# 7segement4digits1badidea-feathershield-m.net
KiCad netlist of a schematic drawn in EAGLE
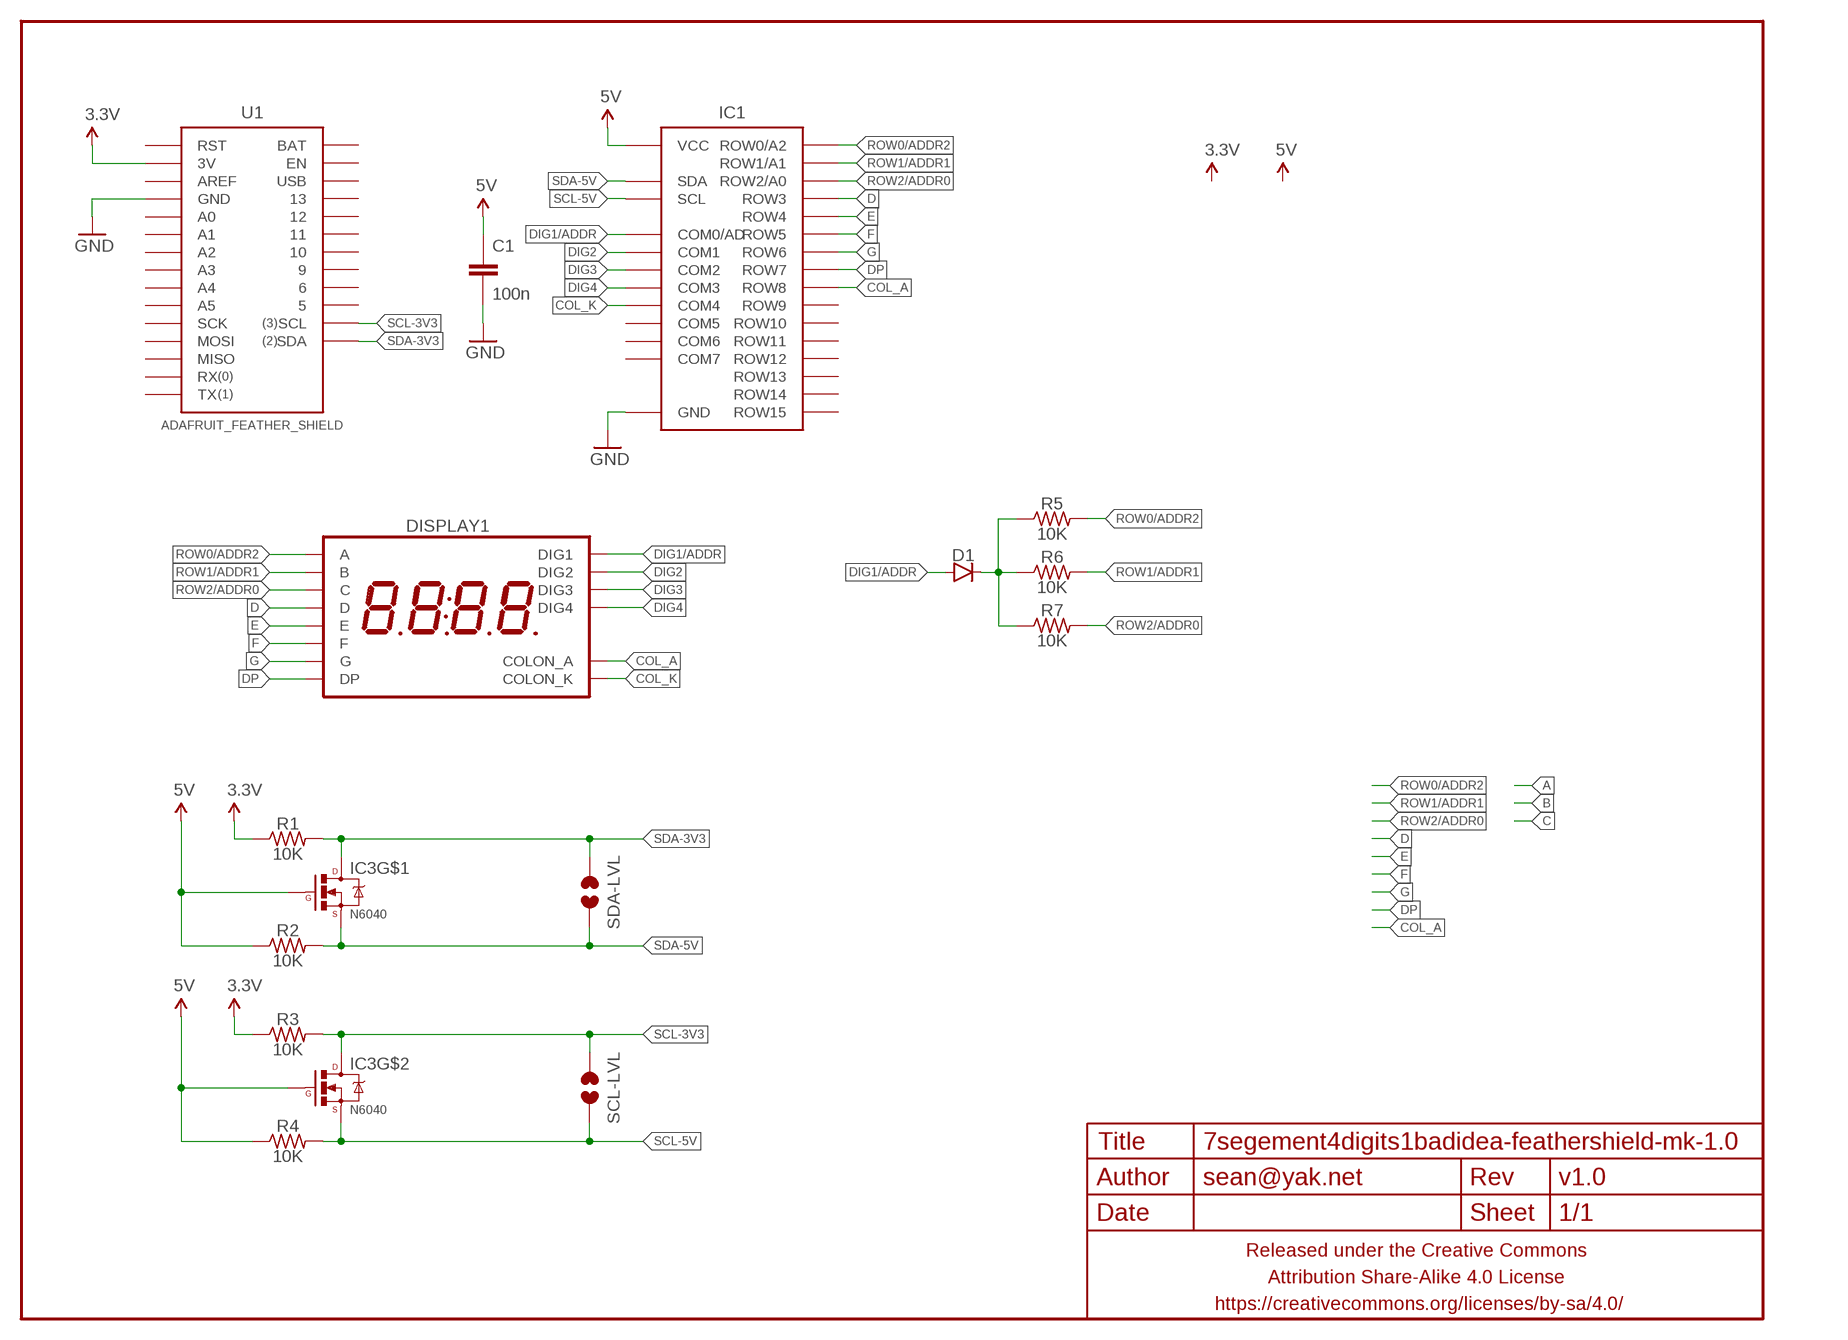
[diagram p0: schematic, sheet 1]

(export (version "E")
  (design (tool "Eeschema 10.0.6"))
  (components
    (comp (ref "C1")
      (value "100n")
      (footprint "eagle-import:C0603")
      (libsource (lib "eagle-import") (part "CAPACITOR-CERAMICC0603"))
    )
    (comp (ref "D1")
      (value "DIODESOT23")
      (footprint "eagle-import:SOT23")
      (libsource (lib "eagle-import") (part "DIODESOT23"))
    )
    (comp (ref "DISPLAY1")
      (value "7SEG_4DIGIT_COLON14.2MM-CC")
      (footprint "eagle-import:7SEG_4DIG_0.56IN_14MM_ADAFRUIT")
      (libsource (lib "eagle-import") (part "7SEG_4DIGIT_COLON14.2MM-CC"))
    )
    (comp (ref "FRAME1")
      (value "FRAME-LETTERNO_PACKAGE")
      (footprint "eagle-import:DUMMY")
      (fields (field (name "DESIGNER") "sean@yak.net") (field (name "VERSION") "v1.0"))
      (libsource (lib "eagle-import") (part "FRAME-LETTERNO_PACKAGE"))
    )
    (comp (ref "IC1")
      (value "HT16K33")
      (footprint "eagle-import:SOIC28W")
      (libsource (lib "eagle-import") (part "HT16K33-28SOIC28W"))
    )
    (comp (ref "IC3")
      (value "N6040")
      (footprint "eagle-import:SO08")
      (libsource (lib "eagle-import") (part "MOSFET-NCHANNEL-DUALSOIC8"))
    )
    (comp (ref "R1")
      (value "10K")
      (footprint "eagle-import:R0603")
      (libsource (lib "eagle-import") (part "RESISTORR0603"))
    )
    (comp (ref "R2")
      (value "10K")
      (footprint "eagle-import:R0603")
      (libsource (lib "eagle-import") (part "RESISTORR0603"))
    )
    (comp (ref "R3")
      (value "10K")
      (footprint "eagle-import:R0603")
      (libsource (lib "eagle-import") (part "RESISTORR0603"))
    )
    (comp (ref "R4")
      (value "10K")
      (footprint "eagle-import:R0603")
      (libsource (lib "eagle-import") (part "RESISTORR0603"))
    )
    (comp (ref "R5")
      (value "10K")
      (footprint "eagle-import:R0603")
      (libsource (lib "eagle-import") (part "RESISTORR0603"))
    )
    (comp (ref "R6")
      (value "10K")
      (footprint "eagle-import:R0603")
      (libsource (lib "eagle-import") (part "RESISTORR0603"))
    )
    (comp (ref "R7")
      (value "10K")
      (footprint "eagle-import:R0603")
      (libsource (lib "eagle-import") (part "RESISTORR0603"))
    )
    (comp (ref "SCL-LVL")
      (value "JUMPER-PAD-2-NOYES_SILK")
      (footprint "eagle-import:PAD-JUMPER-2-NO_YES_SILK")
      (libsource (lib "eagle-import") (part "JUMPER-PAD-2-NOYES_SILK"))
    )
    (comp (ref "SDA-LVL")
      (value "JUMPER-PAD-2-NOYES_SILK")
      (footprint "eagle-import:PAD-JUMPER-2-NO_YES_SILK")
      (libsource (lib "eagle-import") (part "JUMPER-PAD-2-NOYES_SILK"))
    )
    (comp (ref "U1")
      (value "ADAFRUIT_FEATHER_SHIELD")
      (footprint "eagle-import:ADAFRUIT_FEATHER")
      (libsource (lib "eagle-import") (part "ADAFRUIT_FEATHER_SHIELD"))
    )
  )
  (nets
    (net (code "1") (name "3.3V") (class "Default")
      (node (ref "R1") (pin "1") (pinfunction "1_1") (pintype "passive"))
      (node (ref "R3") (pin "1") (pinfunction "1_1") (pintype "passive"))
      (node (ref "U1") (pin "3V") (pinfunction "3V_3V") (pintype "bidirectional"))
    )
    (net (code "2") (name "5V") (class "Default")
      (node (ref "C1") (pin "1") (pinfunction "1_1") (pintype "passive"))
      (node (ref "IC1") (pin "28") (pinfunction "VCC_28") (pintype "bidirectional"))
      (node (ref "IC3") (pin "2") (pinfunction "G_2") (pintype "passive"))
      (node (ref "IC3") (pin "4") (pinfunction "G_4") (pintype "passive"))
      (node (ref "R2") (pin "1") (pinfunction "1_1") (pintype "passive"))
      (node (ref "R4") (pin "1") (pinfunction "1_1") (pintype "passive"))
    )
    (net (code "6") (name "COL_A") (class "Default")
      (node (ref "DISPLAY1") (pin "P$8") (pinfunction "COLON_A_P$8") (pintype "passive"))
      (node (ref "IC1") (pin "17") (pinfunction "ROW8_17") (pintype "bidirectional"))
    )
    (net (code "7") (name "COL_K") (class "Default")
      (node (ref "DISPLAY1") (pin "P$7") (pinfunction "COLON_K_P$7") (pintype "passive"))
      (node (ref "IC1") (pin "6") (pinfunction "COM4_6") (pintype "bidirectional"))
    )
    (net (code "8") (name "D") (class "Default")
      (node (ref "DISPLAY1") (pin "P$2") (pinfunction "D_P$2") (pintype "passive"))
      (node (ref "IC1") (pin "22") (pinfunction "ROW3_22") (pintype "bidirectional"))
    )
    (net (code "9") (name "DIG1{slash}ADDR") (class "Default")
      (node (ref "D1") (pin "1") (pinfunction "A_1") (pintype "passive"))
      (node (ref "DISPLAY1") (pin "P$14") (pinfunction "DIG1_P$14") (pintype "passive"))
      (node (ref "IC1") (pin "2") (pinfunction "COM0/AD_2") (pintype "bidirectional"))
    )
    (net (code "10") (name "DIG2") (class "Default")
      (node (ref "DISPLAY1") (pin "P$11") (pinfunction "DIG2_P$11") (pintype "passive"))
      (node (ref "IC1") (pin "3") (pinfunction "COM1_3") (pintype "bidirectional"))
    )
    (net (code "11") (name "DIG3") (class "Default")
      (node (ref "DISPLAY1") (pin "P$10") (pinfunction "DIG3_P$10") (pintype "passive"))
      (node (ref "IC1") (pin "4") (pinfunction "COM2_4") (pintype "bidirectional"))
    )
    (net (code "12") (name "DIG4") (class "Default")
      (node (ref "DISPLAY1") (pin "P$6") (pinfunction "DIG4_P$6") (pintype "passive"))
      (node (ref "IC1") (pin "5") (pinfunction "COM3_5") (pintype "bidirectional"))
    )
    (net (code "13") (name "DP") (class "Default")
      (node (ref "DISPLAY1") (pin "P$3") (pinfunction "DP_P$3") (pintype "passive"))
      (node (ref "IC1") (pin "18") (pinfunction "ROW7_18") (pintype "bidirectional"))
    )
    (net (code "14") (name "E") (class "Default")
      (node (ref "DISPLAY1") (pin "P$1") (pinfunction "E_P$1") (pintype "passive"))
      (node (ref "IC1") (pin "21") (pinfunction "ROW4_21") (pintype "bidirectional"))
    )
    (net (code "15") (name "F") (class "Default")
      (node (ref "DISPLAY1") (pin "P$12") (pinfunction "F_P$12") (pintype "passive"))
      (node (ref "IC1") (pin "20") (pinfunction "ROW5_20") (pintype "bidirectional"))
    )
    (net (code "16") (name "G") (class "Default")
      (node (ref "DISPLAY1") (pin "P$5") (pinfunction "G_P$5") (pintype "passive"))
      (node (ref "IC1") (pin "19") (pinfunction "ROW6_19") (pintype "bidirectional"))
    )
    (net (code "17") (name "GND") (class "Default")
      (node (ref "C1") (pin "2") (pinfunction "2_2") (pintype "passive"))
      (node (ref "IC1") (pin "1") (pinfunction "GND_1") (pintype "bidirectional"))
      (node (ref "U1") (pin "GND@0") (pinfunction "GND_GND@0") (pintype "bidirectional"))
      (node (ref "U1") (pin "GND@1") (pinfunction "GND_GND@1") (pintype "bidirectional"))
    )
    (net (code "18") (name "Net-(D1-C)") (class "Default")
      (node (ref "D1") (pin "3") (pinfunction "C_3") (pintype "passive"))
      (node (ref "R5") (pin "1") (pinfunction "1_1") (pintype "passive"))
      (node (ref "R6") (pin "1") (pinfunction "1_1") (pintype "passive"))
      (node (ref "R7") (pin "1") (pinfunction "1_1") (pintype "passive"))
    )
    (net (code "19") (name "ROW0{slash}ADDR2") (class "Default")
      (node (ref "DISPLAY1") (pin "P$13") (pinfunction "A_P$13") (pintype "passive"))
      (node (ref "IC1") (pin "25") (pinfunction "ROW0/A2_25") (pintype "bidirectional"))
      (node (ref "R5") (pin "2") (pinfunction "2_2") (pintype "passive"))
    )
    (net (code "20") (name "ROW1{slash}ADDR1") (class "Default")
      (node (ref "DISPLAY1") (pin "P$9") (pinfunction "B_P$9") (pintype "passive"))
      (node (ref "IC1") (pin "24") (pinfunction "ROW1/A1_24") (pintype "bidirectional"))
      (node (ref "R6") (pin "2") (pinfunction "2_2") (pintype "passive"))
    )
    (net (code "21") (name "ROW2{slash}ADDR0") (class "Default")
      (node (ref "DISPLAY1") (pin "P$4") (pinfunction "C_P$4") (pintype "passive"))
      (node (ref "IC1") (pin "23") (pinfunction "ROW2/A0_23") (pintype "bidirectional"))
      (node (ref "R7") (pin "2") (pinfunction "2_2") (pintype "passive"))
    )
    (net (code "22") (name "SCL-3V3") (class "Default")
      (node (ref "IC3") (pin "5") (pinfunction "D_5") (pintype "passive"))
      (node (ref "IC3") (pin "6") (pinfunction "D_6") (pintype "passive"))
      (node (ref "R3") (pin "2") (pinfunction "2_2") (pintype "passive"))
      (node (ref "SCL-LVL") (pin "1") (pinfunction "1_1") (pintype "passive"))
      (node (ref "U1") (pin "SCL") (pinfunction "SCL_SCL") (pintype "bidirectional"))
    )
    (net (code "23") (name "SCL-5V") (class "Default")
      (node (ref "IC1") (pin "26") (pinfunction "SCL_26") (pintype "bidirectional"))
      (node (ref "IC3") (pin "3") (pinfunction "S_3") (pintype "passive"))
      (node (ref "R4") (pin "2") (pinfunction "2_2") (pintype "passive"))
      (node (ref "SCL-LVL") (pin "2") (pinfunction "2_2") (pintype "passive"))
    )
    (net (code "24") (name "SDA-3V3") (class "Default")
      (node (ref "IC3") (pin "7") (pinfunction "D_7") (pintype "passive"))
      (node (ref "IC3") (pin "8") (pinfunction "D_8") (pintype "passive"))
      (node (ref "R1") (pin "2") (pinfunction "2_2") (pintype "passive"))
      (node (ref "SDA-LVL") (pin "1") (pinfunction "1_1") (pintype "passive"))
      (node (ref "U1") (pin "SDA") (pinfunction "SDA_SDA") (pintype "bidirectional"))
    )
    (net (code "25") (name "SDA-5V") (class "Default")
      (node (ref "IC1") (pin "27") (pinfunction "SDA_27") (pintype "bidirectional"))
      (node (ref "IC3") (pin "1") (pinfunction "S_1") (pintype "passive"))
      (node (ref "R2") (pin "2") (pinfunction "2_2") (pintype "passive"))
      (node (ref "SDA-LVL") (pin "2") (pinfunction "2_2") (pintype "passive"))
    )
    (net (code "26") (name "unconnected-(IC1-COM5-Pad7)") (class "Default")
      (node (ref "IC1") (pin "7") (pinfunction "COM5_7") (pintype "bidirectional"))
    )
    (net (code "27") (name "unconnected-(IC1-COM6-Pad8)") (class "Default")
      (node (ref "IC1") (pin "8") (pinfunction "COM6_8") (pintype "bidirectional"))
    )
    (net (code "28") (name "unconnected-(IC1-COM7-Pad9)") (class "Default")
      (node (ref "IC1") (pin "9") (pinfunction "COM7_9") (pintype "bidirectional"))
    )
    (net (code "29") (name "unconnected-(IC1-ROW9-Pad16)") (class "Default")
      (node (ref "IC1") (pin "16") (pinfunction "ROW9_16") (pintype "bidirectional"))
    )
    (net (code "30") (name "unconnected-(IC1-ROW10-Pad15)") (class "Default")
      (node (ref "IC1") (pin "15") (pinfunction "ROW10_15") (pintype "bidirectional"))
    )
    (net (code "31") (name "unconnected-(IC1-ROW11-Pad14)") (class "Default")
      (node (ref "IC1") (pin "14") (pinfunction "ROW11_14") (pintype "bidirectional"))
    )
    (net (code "32") (name "unconnected-(IC1-ROW12-Pad13)") (class "Default")
      (node (ref "IC1") (pin "13") (pinfunction "ROW12_13") (pintype "bidirectional"))
    )
    (net (code "33") (name "unconnected-(IC1-ROW13-Pad12)") (class "Default")
      (node (ref "IC1") (pin "12") (pinfunction "ROW13_12") (pintype "bidirectional"))
    )
    (net (code "34") (name "unconnected-(IC1-ROW14-Pad11)") (class "Default")
      (node (ref "IC1") (pin "11") (pinfunction "ROW14_11") (pintype "bidirectional"))
    )
    (net (code "35") (name "unconnected-(IC1-ROW15-Pad10)") (class "Default")
      (node (ref "IC1") (pin "10") (pinfunction "ROW15_10") (pintype "bidirectional"))
    )
    (net (code "36") (name "unconnected-(U1-Pad5)") (class "Default")
      (node (ref "U1") (pin "5") (pinfunction "5_5") (pintype "bidirectional"))
    )
    (net (code "37") (name "unconnected-(U1-Pad6)") (class "Default")
      (node (ref "U1") (pin "6") (pinfunction "6_6") (pintype "bidirectional"))
    )
    (net (code "38") (name "unconnected-(U1-Pad9)") (class "Default")
      (node (ref "U1") (pin "9") (pinfunction "9_9") (pintype "bidirectional"))
    )
    (net (code "39") (name "unconnected-(U1-Pad10)") (class "Default")
      (node (ref "U1") (pin "10") (pinfunction "10_10") (pintype "bidirectional"))
    )
    (net (code "40") (name "unconnected-(U1-Pad11)") (class "Default")
      (node (ref "U1") (pin "11") (pinfunction "11_11") (pintype "bidirectional"))
    )
    (net (code "41") (name "unconnected-(U1-Pad12)") (class "Default")
      (node (ref "U1") (pin "12") (pinfunction "12_12") (pintype "bidirectional"))
    )
    (net (code "42") (name "unconnected-(U1-Pad13)") (class "Default")
      (node (ref "U1") (pin "13") (pinfunction "13_13") (pintype "bidirectional"))
    )
    (net (code "43") (name "unconnected-(U1-PadA0)") (class "Default")
      (node (ref "U1") (pin "A0") (pinfunction "A0_A0") (pintype "bidirectional"))
    )
    (net (code "44") (name "unconnected-(U1-PadA1)") (class "Default")
      (node (ref "U1") (pin "A1") (pinfunction "A1_A1") (pintype "bidirectional"))
    )
    (net (code "45") (name "unconnected-(U1-PadA2)") (class "Default")
      (node (ref "U1") (pin "A2") (pinfunction "A2_A2") (pintype "bidirectional"))
    )
    (net (code "46") (name "unconnected-(U1-PadA3)") (class "Default")
      (node (ref "U1") (pin "A3") (pinfunction "A3_A3") (pintype "bidirectional"))
    )
    (net (code "47") (name "unconnected-(U1-PadA4)") (class "Default")
      (node (ref "U1") (pin "A4") (pinfunction "A4_A4") (pintype "bidirectional"))
    )
    (net (code "48") (name "unconnected-(U1-PadA5)") (class "Default")
      (node (ref "U1") (pin "A5") (pinfunction "A5_A5") (pintype "bidirectional"))
    )
    (net (code "49") (name "unconnected-(U1-PadAREF)") (class "Default")
      (node (ref "U1") (pin "AREF") (pinfunction "AREF_AREF") (pintype "bidirectional"))
    )
    (net (code "50") (name "unconnected-(U1-PadBAT)") (class "Default")
      (node (ref "U1") (pin "BAT") (pinfunction "BAT_BAT") (pintype "bidirectional"))
    )
    (net (code "51") (name "unconnected-(U1-PadEN)") (class "Default")
      (node (ref "U1") (pin "EN") (pinfunction "EN_EN") (pintype "bidirectional"))
    )
    (net (code "52") (name "unconnected-(U1-PadMISO)") (class "Default")
      (node (ref "U1") (pin "MISO") (pinfunction "MISO_MISO") (pintype "bidirectional"))
    )
    (net (code "53") (name "unconnected-(U1-PadMOSI)") (class "Default")
      (node (ref "U1") (pin "MOSI") (pinfunction "MOSI_MOSI") (pintype "bidirectional"))
    )
    (net (code "54") (name "unconnected-(U1-PadRST)") (class "Default")
      (node (ref "U1") (pin "RST") (pinfunction "RST_RST") (pintype "bidirectional"))
    )
    (net (code "55") (name "unconnected-(U1-PadRX)") (class "Default")
      (node (ref "U1") (pin "RX") (pinfunction "RX_RX") (pintype "bidirectional"))
    )
    (net (code "56") (name "unconnected-(U1-PadSCK)") (class "Default")
      (node (ref "U1") (pin "SCK") (pinfunction "SCK_SCK") (pintype "bidirectional"))
    )
    (net (code "57") (name "unconnected-(U1-PadTX)") (class "Default")
      (node (ref "U1") (pin "TX") (pinfunction "TX_TX") (pintype "bidirectional"))
    )
    (net (code "58") (name "unconnected-(U1-PadUSB)") (class "Default")
      (node (ref "U1") (pin "USB") (pinfunction "USB_USB") (pintype "bidirectional"))
    )
  )
)
